# led_mask.net
KiCad netlist of a schematic drawn in EAGLE
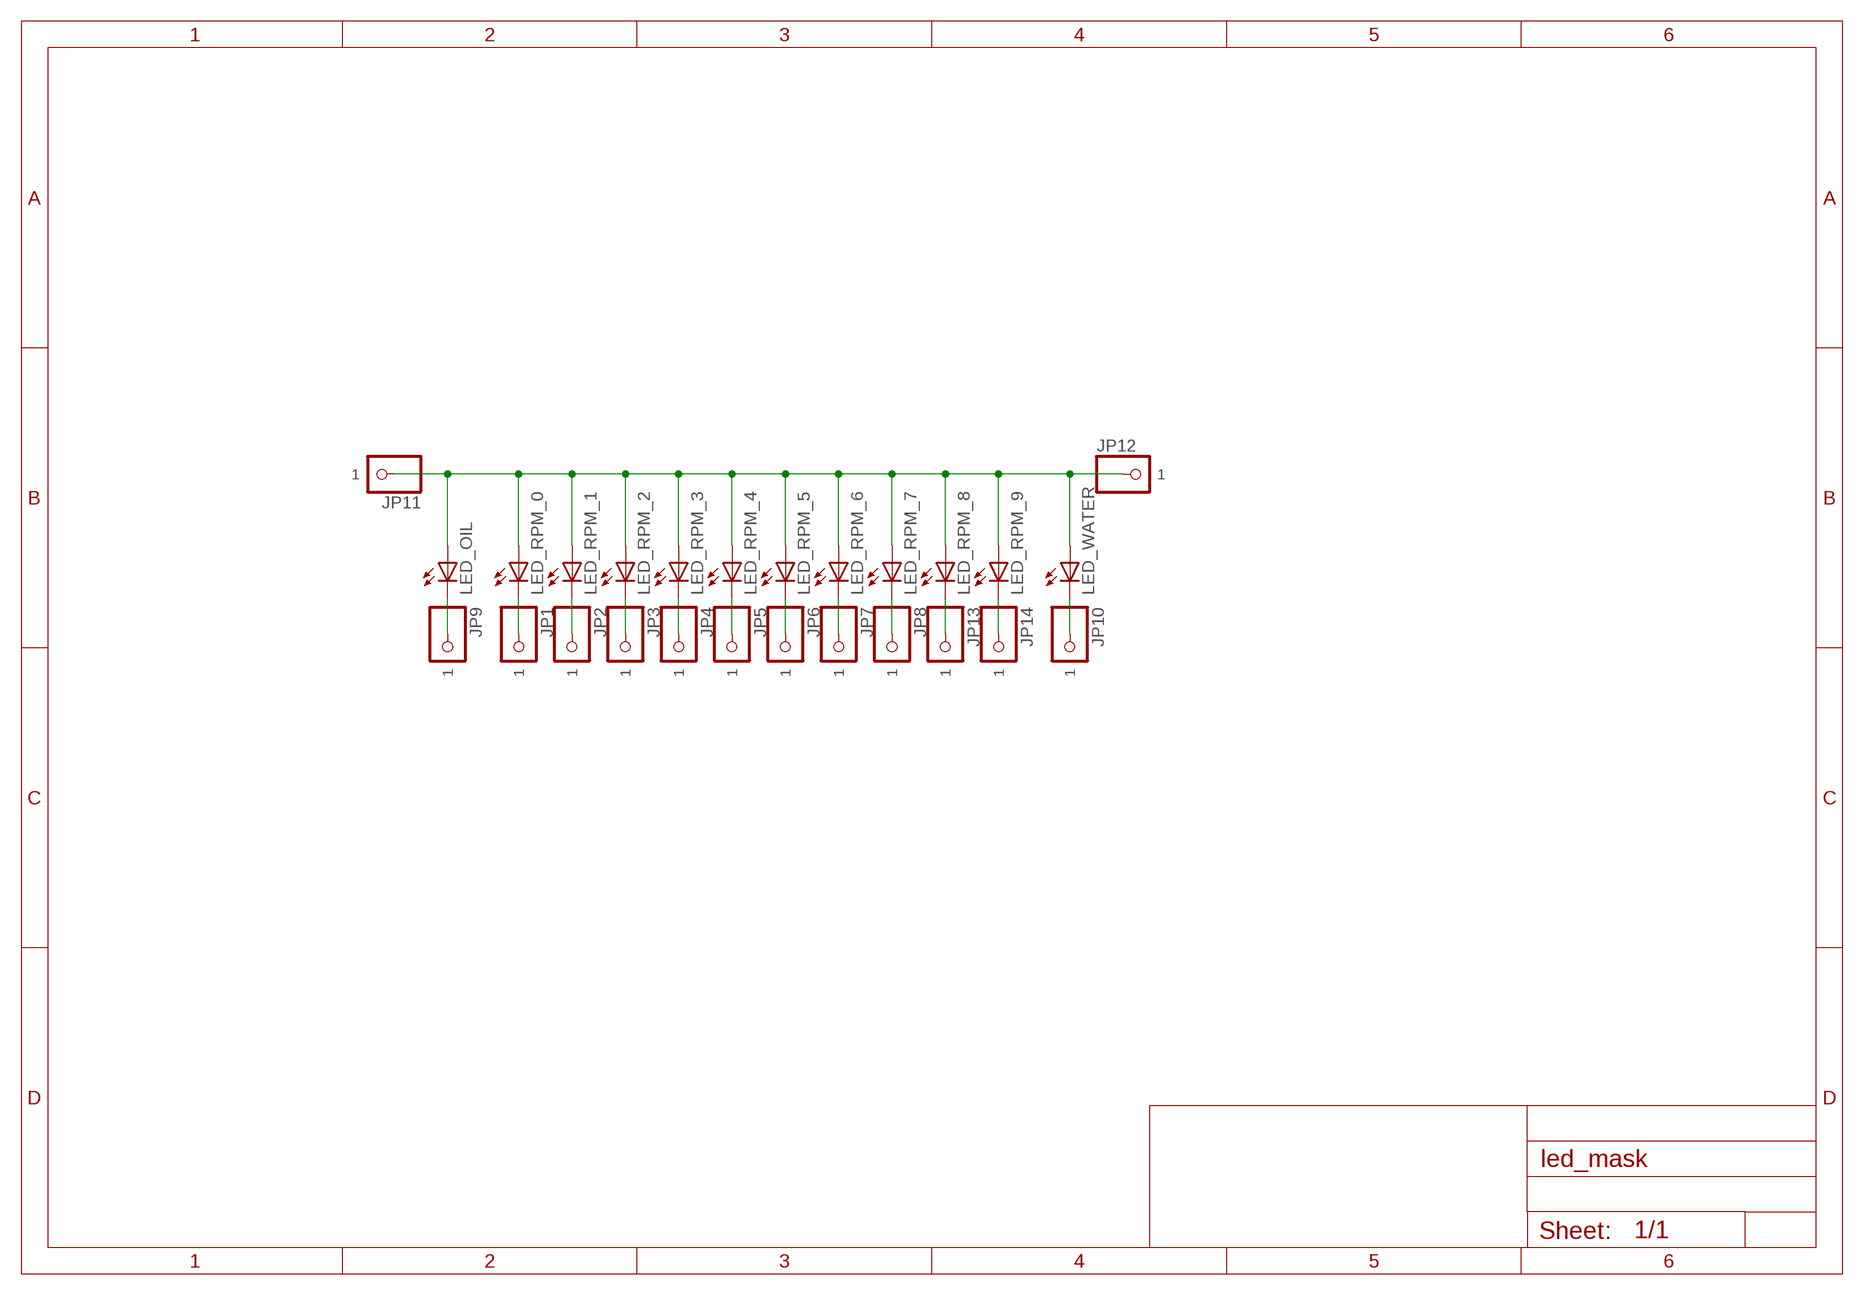
[diagram p0: schematic, sheet 1]

(export (version "E")
  (design (tool "Eeschema 10.0.6"))
  (components
    (comp (ref "JP1")
      (value "PINHD-1X11.5X2.5MM_SMD")
      (footprint "eagle-import:1XSMD1.5X2.5MM")
      (libsource (lib "eagle-import") (part "PINHD-1X11.5X2.5MM_SMD"))
    )
    (comp (ref "JP2")
      (value "PINHD-1X11.5X2.5MM_SMD")
      (footprint "eagle-import:1XSMD1.5X2.5MM")
      (libsource (lib "eagle-import") (part "PINHD-1X11.5X2.5MM_SMD"))
    )
    (comp (ref "JP3")
      (value "PINHD-1X11.5X2.5MM_SMD")
      (footprint "eagle-import:1XSMD1.5X2.5MM")
      (libsource (lib "eagle-import") (part "PINHD-1X11.5X2.5MM_SMD"))
    )
    (comp (ref "JP4")
      (value "PINHD-1X11.5X2.5MM_SMD")
      (footprint "eagle-import:1XSMD1.5X2.5MM")
      (libsource (lib "eagle-import") (part "PINHD-1X11.5X2.5MM_SMD"))
    )
    (comp (ref "JP5")
      (value "PINHD-1X11.5X2.5MM_SMD")
      (footprint "eagle-import:1XSMD1.5X2.5MM")
      (libsource (lib "eagle-import") (part "PINHD-1X11.5X2.5MM_SMD"))
    )
    (comp (ref "JP6")
      (value "PINHD-1X11.5X2.5MM_SMD")
      (footprint "eagle-import:1XSMD1.5X2.5MM")
      (libsource (lib "eagle-import") (part "PINHD-1X11.5X2.5MM_SMD"))
    )
    (comp (ref "JP7")
      (value "PINHD-1X11.5X2.5MM_SMD")
      (footprint "eagle-import:1XSMD1.5X2.5MM")
      (libsource (lib "eagle-import") (part "PINHD-1X11.5X2.5MM_SMD"))
    )
    (comp (ref "JP8")
      (value "PINHD-1X11.5X2.5MM_SMD")
      (footprint "eagle-import:1XSMD1.5X2.5MM")
      (libsource (lib "eagle-import") (part "PINHD-1X11.5X2.5MM_SMD"))
    )
    (comp (ref "JP9")
      (value "PINHD-1X11.5X2.5MM_SMD")
      (footprint "eagle-import:1XSMD1.5X2.5MM")
      (libsource (lib "eagle-import") (part "PINHD-1X11.5X2.5MM_SMD"))
    )
    (comp (ref "JP10")
      (value "PINHD-1X11.5X2.5MM_SMD")
      (footprint "eagle-import:1XSMD1.5X2.5MM")
      (libsource (lib "eagle-import") (part "PINHD-1X11.5X2.5MM_SMD"))
    )
    (comp (ref "JP11")
      (value "PINHD-1X11.5X2.5MM_SMD")
      (footprint "eagle-import:1XSMD1.5X2.5MM")
      (libsource (lib "eagle-import") (part "PINHD-1X11.5X2.5MM_SMD"))
    )
    (comp (ref "JP12")
      (value "PINHD-1X11.5X2.5MM_SMD")
      (footprint "eagle-import:1XSMD1.5X2.5MM")
      (libsource (lib "eagle-import") (part "PINHD-1X11.5X2.5MM_SMD"))
    )
    (comp (ref "JP13")
      (value "PINHD-1X11.5X2.5MM_SMD")
      (footprint "eagle-import:1XSMD1.5X2.5MM")
      (libsource (lib "eagle-import") (part "PINHD-1X11.5X2.5MM_SMD"))
    )
    (comp (ref "JP14")
      (value "PINHD-1X11.5X2.5MM_SMD")
      (footprint "eagle-import:1XSMD1.5X2.5MM")
      (libsource (lib "eagle-import") (part "PINHD-1X11.5X2.5MM_SMD"))
    )
    (comp (ref "LED_OIL")
      (value "LED3MM")
      (footprint "eagle-import:LED3MM")
      (libsource (lib "eagle-import") (part "LED3MM"))
    )
    (comp (ref "LED_RPM_0")
      (value "LED3MM")
      (footprint "eagle-import:LED3MM")
      (libsource (lib "eagle-import") (part "LED3MM"))
    )
    (comp (ref "LED_RPM_1")
      (value "LED3MM")
      (footprint "eagle-import:LED3MM")
      (libsource (lib "eagle-import") (part "LED3MM"))
    )
    (comp (ref "LED_RPM_2")
      (value "LED3MM")
      (footprint "eagle-import:LED3MM")
      (libsource (lib "eagle-import") (part "LED3MM"))
    )
    (comp (ref "LED_RPM_3")
      (value "LED3MM")
      (footprint "eagle-import:LED3MM")
      (libsource (lib "eagle-import") (part "LED3MM"))
    )
    (comp (ref "LED_RPM_4")
      (value "LED3MM")
      (footprint "eagle-import:LED3MM")
      (libsource (lib "eagle-import") (part "LED3MM"))
    )
    (comp (ref "LED_RPM_5")
      (value "LED3MM")
      (footprint "eagle-import:LED3MM")
      (libsource (lib "eagle-import") (part "LED3MM"))
    )
    (comp (ref "LED_RPM_6")
      (value "LED3MM")
      (footprint "eagle-import:LED3MM")
      (libsource (lib "eagle-import") (part "LED3MM"))
    )
    (comp (ref "LED_RPM_7")
      (value "LED3MM")
      (footprint "eagle-import:LED3MM")
      (libsource (lib "eagle-import") (part "LED3MM"))
    )
    (comp (ref "LED_RPM_8")
      (value "LED3MM")
      (footprint "eagle-import:LED3MM")
      (libsource (lib "eagle-import") (part "LED3MM"))
    )
    (comp (ref "LED_RPM_9")
      (value "LED3MM")
      (footprint "eagle-import:LED3MM")
      (libsource (lib "eagle-import") (part "LED3MM"))
    )
    (comp (ref "LED_WATER")
      (value "LED3MM")
      (footprint "eagle-import:LED3MM")
      (libsource (lib "eagle-import") (part "LED3MM"))
    )
  )
  (nets
    (net (code "1") (name "Net-(JP1-1)") (class "Default")
      (node (ref "JP1") (pin "P$1") (pinfunction "1_P$1") (pintype "passive"))
      (node (ref "LED_RPM_0") (pin "K") (pinfunction "C_K") (pintype "passive"))
    )
    (net (code "2") (name "Net-(JP2-1)") (class "Default")
      (node (ref "JP2") (pin "P$1") (pinfunction "1_P$1") (pintype "passive"))
      (node (ref "LED_RPM_1") (pin "K") (pinfunction "C_K") (pintype "passive"))
    )
    (net (code "3") (name "Net-(JP3-1)") (class "Default")
      (node (ref "JP3") (pin "P$1") (pinfunction "1_P$1") (pintype "passive"))
      (node (ref "LED_RPM_2") (pin "K") (pinfunction "C_K") (pintype "passive"))
    )
    (net (code "4") (name "Net-(JP4-1)") (class "Default")
      (node (ref "JP4") (pin "P$1") (pinfunction "1_P$1") (pintype "passive"))
      (node (ref "LED_RPM_3") (pin "K") (pinfunction "C_K") (pintype "passive"))
    )
    (net (code "5") (name "Net-(JP5-1)") (class "Default")
      (node (ref "JP5") (pin "P$1") (pinfunction "1_P$1") (pintype "passive"))
      (node (ref "LED_RPM_4") (pin "K") (pinfunction "C_K") (pintype "passive"))
    )
    (net (code "6") (name "Net-(JP6-1)") (class "Default")
      (node (ref "JP6") (pin "P$1") (pinfunction "1_P$1") (pintype "passive"))
      (node (ref "LED_RPM_5") (pin "K") (pinfunction "C_K") (pintype "passive"))
    )
    (net (code "7") (name "Net-(JP7-1)") (class "Default")
      (node (ref "JP7") (pin "P$1") (pinfunction "1_P$1") (pintype "passive"))
      (node (ref "LED_RPM_6") (pin "K") (pinfunction "C_K") (pintype "passive"))
    )
    (net (code "8") (name "Net-(JP8-1)") (class "Default")
      (node (ref "JP8") (pin "P$1") (pinfunction "1_P$1") (pintype "passive"))
      (node (ref "LED_RPM_7") (pin "K") (pinfunction "C_K") (pintype "passive"))
    )
    (net (code "9") (name "Net-(JP9-1)") (class "Default")
      (node (ref "JP9") (pin "P$1") (pinfunction "1_P$1") (pintype "passive"))
      (node (ref "LED_OIL") (pin "K") (pinfunction "C_K") (pintype "passive"))
    )
    (net (code "10") (name "Net-(JP10-1)") (class "Default")
      (node (ref "JP10") (pin "P$1") (pinfunction "1_P$1") (pintype "passive"))
      (node (ref "LED_WATER") (pin "K") (pinfunction "C_K") (pintype "passive"))
    )
    (net (code "11") (name "Net-(JP11-1)") (class "Default")
      (node (ref "JP11") (pin "P$1") (pinfunction "1_P$1") (pintype "passive"))
      (node (ref "JP12") (pin "P$1") (pinfunction "1_P$1") (pintype "passive"))
      (node (ref "LED_OIL") (pin "A") (pinfunction "A_A") (pintype "passive"))
      (node (ref "LED_RPM_0") (pin "A") (pinfunction "A_A") (pintype "passive"))
      (node (ref "LED_RPM_1") (pin "A") (pinfunction "A_A") (pintype "passive"))
      (node (ref "LED_RPM_2") (pin "A") (pinfunction "A_A") (pintype "passive"))
      (node (ref "LED_RPM_3") (pin "A") (pinfunction "A_A") (pintype "passive"))
      (node (ref "LED_RPM_4") (pin "A") (pinfunction "A_A") (pintype "passive"))
      (node (ref "LED_RPM_5") (pin "A") (pinfunction "A_A") (pintype "passive"))
      (node (ref "LED_RPM_6") (pin "A") (pinfunction "A_A") (pintype "passive"))
      (node (ref "LED_RPM_7") (pin "A") (pinfunction "A_A") (pintype "passive"))
      (node (ref "LED_RPM_8") (pin "A") (pinfunction "A_A") (pintype "passive"))
      (node (ref "LED_RPM_9") (pin "A") (pinfunction "A_A") (pintype "passive"))
      (node (ref "LED_WATER") (pin "A") (pinfunction "A_A") (pintype "passive"))
    )
    (net (code "12") (name "Net-(JP13-1)") (class "Default")
      (node (ref "JP13") (pin "P$1") (pinfunction "1_P$1") (pintype "passive"))
      (node (ref "LED_RPM_8") (pin "K") (pinfunction "C_K") (pintype "passive"))
    )
    (net (code "13") (name "Net-(JP14-1)") (class "Default")
      (node (ref "JP14") (pin "P$1") (pinfunction "1_P$1") (pintype "passive"))
      (node (ref "LED_RPM_9") (pin "K") (pinfunction "C_K") (pintype "passive"))
    )
  )
)
